# keyModule.net
KiCad netlist of a schematic drawn in Altium Designer
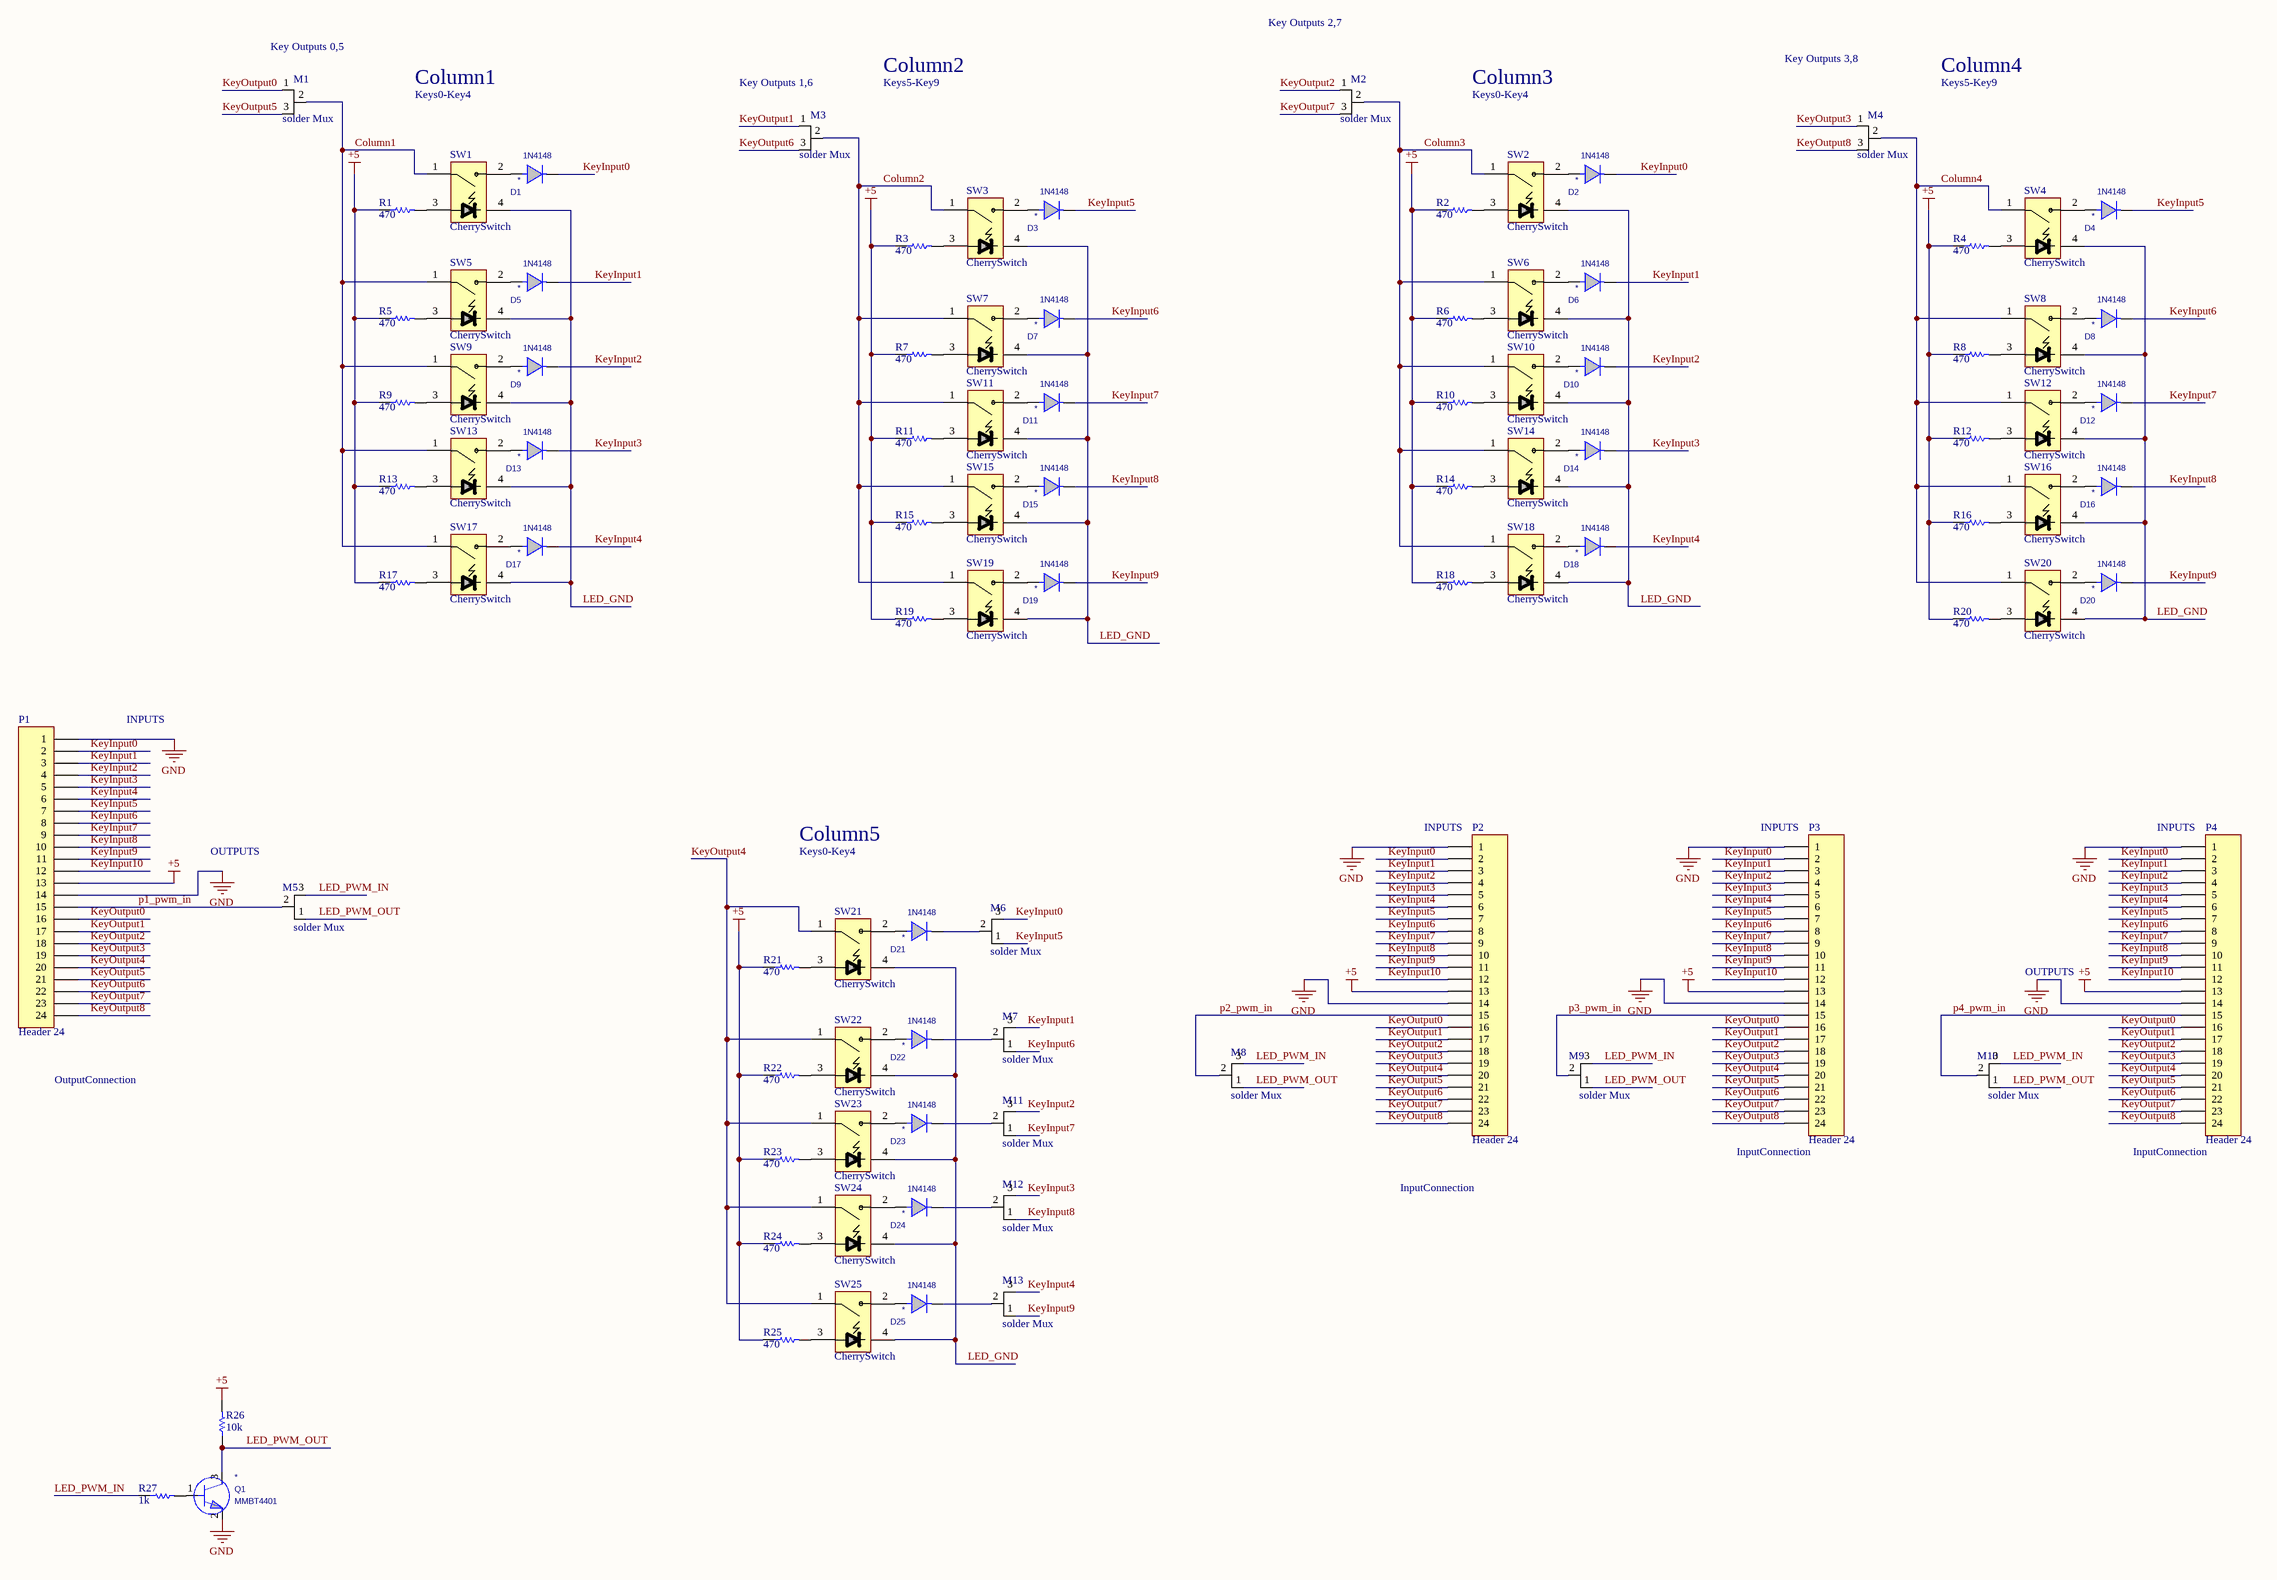
[diagram p0: keyModule.SchDoc]

(export (version "E")
  (design (tool "Eeschema 10.0.6"))
  (components
    (comp (ref "D1")
      (value "1N4148")
      (footprint "axial with SOD-323F")
      (description "Diode, 1N4148, 75V, 0.4 in., DO-35, 150mA, Switching, 500mW, Any")
      (fields (field (name "DNS") "*") (field (name "VOLTAGE") "75V") (field (name "CHECKEDBY") "B. Lyon"))
      (libsource (lib "bome") (part "1N4148"))
    )
    (comp (ref "D2")
      (value "1N4148")
      (footprint "axial with SOD-323F")
      (description "Diode, 1N4148, 75V, 0.4 in., DO-35, 150mA, Switching, 500mW, Any")
      (fields (field (name "DNS") "*") (field (name "VOLTAGE") "75V") (field (name "CHECKEDBY") "B. Lyon"))
      (libsource (lib "bome") (part "1N4148"))
    )
    (comp (ref "D3")
      (value "1N4148")
      (footprint "axial with SOD-323F")
      (description "Diode, 1N4148, 75V, 0.4 in., DO-35, 150mA, Switching, 500mW, Any")
      (fields (field (name "DNS") "*") (field (name "VOLTAGE") "75V") (field (name "CHECKEDBY") "B. Lyon"))
      (libsource (lib "bome") (part "1N4148"))
    )
    (comp (ref "D4")
      (value "1N4148")
      (footprint "axial with SOD-323F")
      (description "Diode, 1N4148, 75V, 0.4 in., DO-35, 150mA, Switching, 500mW, Any")
      (fields (field (name "DNS") "*") (field (name "VOLTAGE") "75V") (field (name "CHECKEDBY") "B. Lyon"))
      (libsource (lib "bome") (part "1N4148"))
    )
    (comp (ref "D5")
      (value "1N4148")
      (footprint "axial with SOD-323F")
      (description "Diode, 1N4148, 75V, 0.4 in., DO-35, 150mA, Switching, 500mW, Any")
      (fields (field (name "DNS") "*") (field (name "VOLTAGE") "75V") (field (name "CHECKEDBY") "B. Lyon"))
      (libsource (lib "bome") (part "1N4148"))
    )
    (comp (ref "D6")
      (value "1N4148")
      (footprint "axial with SOD-323F")
      (description "Diode, 1N4148, 75V, 0.4 in., DO-35, 150mA, Switching, 500mW, Any")
      (fields (field (name "DNS") "*") (field (name "VOLTAGE") "75V") (field (name "CHECKEDBY") "B. Lyon"))
      (libsource (lib "bome") (part "1N4148"))
    )
    (comp (ref "D7")
      (value "1N4148")
      (footprint "axial with SOD-323F")
      (description "Diode, 1N4148, 75V, 0.4 in., DO-35, 150mA, Switching, 500mW, Any")
      (fields (field (name "DNS") "*") (field (name "VOLTAGE") "75V") (field (name "CHECKEDBY") "B. Lyon"))
      (libsource (lib "bome") (part "1N4148"))
    )
    (comp (ref "D8")
      (value "1N4148")
      (footprint "axial with SOD-323F")
      (description "Diode, 1N4148, 75V, 0.4 in., DO-35, 150mA, Switching, 500mW, Any")
      (fields (field (name "DNS") "*") (field (name "VOLTAGE") "75V") (field (name "CHECKEDBY") "B. Lyon"))
      (libsource (lib "bome") (part "1N4148"))
    )
    (comp (ref "D9")
      (value "1N4148")
      (footprint "axial with SOD-323F")
      (description "Diode, 1N4148, 75V, 0.4 in., DO-35, 150mA, Switching, 500mW, Any")
      (fields (field (name "DNS") "*") (field (name "VOLTAGE") "75V") (field (name "CHECKEDBY") "B. Lyon"))
      (libsource (lib "bome") (part "1N4148"))
    )
    (comp (ref "D10")
      (value "1N4148")
      (footprint "axial with SOD-323F")
      (description "Diode, 1N4148, 75V, 0.4 in., DO-35, 150mA, Switching, 500mW, Any")
      (fields (field (name "DNS") "*") (field (name "VOLTAGE") "75V") (field (name "CHECKEDBY") "B. Lyon"))
      (libsource (lib "bome") (part "1N4148"))
    )
    (comp (ref "D11")
      (value "1N4148")
      (footprint "axial with SOD-323F")
      (description "Diode, 1N4148, 75V, 0.4 in., DO-35, 150mA, Switching, 500mW, Any")
      (fields (field (name "DNS") "*") (field (name "VOLTAGE") "75V") (field (name "CHECKEDBY") "B. Lyon"))
      (libsource (lib "bome") (part "1N4148"))
    )
    (comp (ref "D12")
      (value "1N4148")
      (footprint "axial with SOD-323F")
      (description "Diode, 1N4148, 75V, 0.4 in., DO-35, 150mA, Switching, 500mW, Any")
      (fields (field (name "DNS") "*") (field (name "VOLTAGE") "75V") (field (name "CHECKEDBY") "B. Lyon"))
      (libsource (lib "bome") (part "1N4148"))
    )
    (comp (ref "D13")
      (value "1N4148")
      (footprint "axial with SOD-323F")
      (description "Diode, 1N4148, 75V, 0.4 in., DO-35, 150mA, Switching, 500mW, Any")
      (fields (field (name "DNS") "*") (field (name "VOLTAGE") "75V") (field (name "CHECKEDBY") "B. Lyon"))
      (libsource (lib "bome") (part "1N4148"))
    )
    (comp (ref "D14")
      (value "1N4148")
      (footprint "axial with SOD-323F")
      (description "Diode, 1N4148, 75V, 0.4 in., DO-35, 150mA, Switching, 500mW, Any")
      (fields (field (name "DNS") "*") (field (name "VOLTAGE") "75V") (field (name "CHECKEDBY") "B. Lyon"))
      (libsource (lib "bome") (part "1N4148"))
    )
    (comp (ref "D15")
      (value "1N4148")
      (footprint "axial with SOD-323F")
      (description "Diode, 1N4148, 75V, 0.4 in., DO-35, 150mA, Switching, 500mW, Any")
      (fields (field (name "DNS") "*") (field (name "VOLTAGE") "75V") (field (name "CHECKEDBY") "B. Lyon"))
      (libsource (lib "bome") (part "1N4148"))
    )
    (comp (ref "D16")
      (value "1N4148")
      (footprint "axial with SOD-323F")
      (description "Diode, 1N4148, 75V, 0.4 in., DO-35, 150mA, Switching, 500mW, Any")
      (fields (field (name "DNS") "*") (field (name "VOLTAGE") "75V") (field (name "CHECKEDBY") "B. Lyon"))
      (libsource (lib "bome") (part "1N4148"))
    )
    (comp (ref "D17")
      (value "1N4148")
      (footprint "axial with SOD-323F")
      (description "Diode, 1N4148, 75V, 0.4 in., DO-35, 150mA, Switching, 500mW, Any")
      (fields (field (name "DNS") "*") (field (name "VOLTAGE") "75V") (field (name "CHECKEDBY") "B. Lyon"))
      (libsource (lib "bome") (part "1N4148"))
    )
    (comp (ref "D18")
      (value "1N4148")
      (footprint "axial with SOD-323F")
      (description "Diode, 1N4148, 75V, 0.4 in., DO-35, 150mA, Switching, 500mW, Any")
      (fields (field (name "DNS") "*") (field (name "VOLTAGE") "75V") (field (name "CHECKEDBY") "B. Lyon"))
      (libsource (lib "bome") (part "1N4148"))
    )
    (comp (ref "D19")
      (value "1N4148")
      (footprint "axial with SOD-323F")
      (description "Diode, 1N4148, 75V, 0.4 in., DO-35, 150mA, Switching, 500mW, Any")
      (fields (field (name "DNS") "*") (field (name "VOLTAGE") "75V") (field (name "CHECKEDBY") "B. Lyon"))
      (libsource (lib "bome") (part "1N4148"))
    )
    (comp (ref "D20")
      (value "1N4148")
      (footprint "axial with SOD-323F")
      (description "Diode, 1N4148, 75V, 0.4 in., DO-35, 150mA, Switching, 500mW, Any")
      (fields (field (name "DNS") "*") (field (name "VOLTAGE") "75V") (field (name "CHECKEDBY") "B. Lyon"))
      (libsource (lib "bome") (part "1N4148"))
    )
    (comp (ref "D21")
      (value "1N4148")
      (footprint "axial with SOD-323F")
      (description "Diode, 1N4148, 75V, 0.4 in., DO-35, 150mA, Switching, 500mW, Any")
      (fields (field (name "DNS") "*") (field (name "VOLTAGE") "75V") (field (name "CHECKEDBY") "B. Lyon"))
      (libsource (lib "bome") (part "1N4148"))
    )
    (comp (ref "D22")
      (value "1N4148")
      (footprint "axial with SOD-323F")
      (description "Diode, 1N4148, 75V, 0.4 in., DO-35, 150mA, Switching, 500mW, Any")
      (fields (field (name "DNS") "*") (field (name "VOLTAGE") "75V") (field (name "CHECKEDBY") "B. Lyon"))
      (libsource (lib "bome") (part "1N4148"))
    )
    (comp (ref "D23")
      (value "1N4148")
      (footprint "axial with SOD-323F")
      (description "Diode, 1N4148, 75V, 0.4 in., DO-35, 150mA, Switching, 500mW, Any")
      (fields (field (name "DNS") "*") (field (name "VOLTAGE") "75V") (field (name "CHECKEDBY") "B. Lyon"))
      (libsource (lib "bome") (part "1N4148"))
    )
    (comp (ref "D24")
      (value "1N4148")
      (footprint "axial with SOD-323F")
      (description "Diode, 1N4148, 75V, 0.4 in., DO-35, 150mA, Switching, 500mW, Any")
      (fields (field (name "DNS") "*") (field (name "VOLTAGE") "75V") (field (name "CHECKEDBY") "B. Lyon"))
      (libsource (lib "bome") (part "1N4148"))
    )
    (comp (ref "D25")
      (value "1N4148")
      (footprint "axial with SOD-323F")
      (description "Diode, 1N4148, 75V, 0.4 in., DO-35, 150mA, Switching, 500mW, Any")
      (fields (field (name "DNS") "*") (field (name "VOLTAGE") "75V") (field (name "CHECKEDBY") "B. Lyon"))
      (libsource (lib "bome") (part "1N4148"))
    )
    (comp (ref "M1")
      (value "solder Mux")
      (footprint "SolderSelect")
      (libsource (lib "mainBoardLib") (part "solder Mux"))
    )
    (comp (ref "M2")
      (value "solder Mux")
      (footprint "SolderSelect")
      (libsource (lib "mainBoardLib") (part "solder Mux"))
    )
    (comp (ref "M3")
      (value "solder Mux")
      (footprint "SolderSelect")
      (libsource (lib "mainBoardLib") (part "solder Mux"))
    )
    (comp (ref "M4")
      (value "solder Mux")
      (footprint "SolderSelect")
      (libsource (lib "mainBoardLib") (part "solder Mux"))
    )
    (comp (ref "M5")
      (value "solder Mux")
      (footprint "SolderSelect")
      (libsource (lib "mainBoardLib") (part "solder Mux"))
    )
    (comp (ref "M6")
      (value "solder Mux")
      (footprint "SolderSelect")
      (libsource (lib "mainBoardLib") (part "solder Mux"))
    )
    (comp (ref "M7")
      (value "solder Mux")
      (footprint "SolderSelect")
      (libsource (lib "mainBoardLib") (part "solder Mux"))
    )
    (comp (ref "M8")
      (value "solder Mux")
      (footprint "SolderSelect")
      (libsource (lib "mainBoardLib") (part "solder Mux"))
    )
    (comp (ref "M9")
      (value "solder Mux")
      (footprint "SolderSelect")
      (libsource (lib "mainBoardLib") (part "solder Mux"))
    )
    (comp (ref "M10")
      (value "solder Mux")
      (footprint "SolderSelect")
      (libsource (lib "mainBoardLib") (part "solder Mux"))
    )
    (comp (ref "M11")
      (value "solder Mux")
      (footprint "SolderSelect")
      (libsource (lib "mainBoardLib") (part "solder Mux"))
    )
    (comp (ref "M12")
      (value "solder Mux")
      (footprint "SolderSelect")
      (libsource (lib "mainBoardLib") (part "solder Mux"))
    )
    (comp (ref "M13")
      (value "solder Mux")
      (footprint "SolderSelect")
      (libsource (lib "mainBoardLib") (part "solder Mux"))
    )
    (comp (ref "P1")
      (value "Header 24")
      (footprint "HDR1X24")
      (description "Header, 24-Pin")
      (fields (field (name "PUBLISHER") "Altium Limited"))
      (libsource (lib "") (part "Header 24_1"))
    )
    (comp (ref "P2")
      (value "Header 24")
      (footprint "HDR1X24")
      (description "Header, 24-Pin")
      (fields (field (name "PUBLISHER") "Altium Limited"))
      (libsource (lib "Miscellaneous Connectors") (part "Header 24"))
    )
    (comp (ref "P3")
      (value "Header 24")
      (footprint "HDR1X24")
      (description "Header, 24-Pin")
      (fields (field (name "PUBLISHER") "Altium Limited"))
      (libsource (lib "Miscellaneous Connectors") (part "Header 24"))
    )
    (comp (ref "P4")
      (value "Header 24")
      (footprint "HDR1X24")
      (description "Header, 24-Pin")
      (fields (field (name "PUBLISHER") "Altium Limited"))
      (libsource (lib "Miscellaneous Connectors") (part "Header 24"))
    )
    (comp (ref "Q1")
      (value "MMBT4401")
      (footprint "SOT23-3")
      (description "Transistor, MMBT4401, 40V, SOT23-3, 500mA, NPN, Transistor, On Semi: MMBT4401LT1")
      (fields
        (field (name "DNS") "*")
        (field (name "VOLTAGE") "40V")
        (field (name "Comment") "NPN_TRANSISTOR")
        (field (name "CHECKEDBY") "gdeguzman")
        (field (name "CREATEDBY") "Mike Tyger")
        (field (name "LASTUPDATEDBY") "Mike Tyger")
      )
      (libsource (lib "bome") (part "NPN_TRANSISTOR"))
    )
    (comp (ref "R1")
      (value "470")
      (footprint "RESC2012L")
      (description "Semiconductor Resistor")
      (fields (field (name "Comment") "Res Semi") (field (name "PUBLISHER") "Altium Limited"))
      (libsource (lib "Miscellaneous Devices") (part "Res Semi"))
    )
    (comp (ref "R2")
      (value "470")
      (footprint "RESC2012L")
      (description "Semiconductor Resistor")
      (fields (field (name "Comment") "Res Semi") (field (name "PUBLISHER") "Altium Limited"))
      (libsource (lib "Miscellaneous Devices") (part "Res Semi"))
    )
    (comp (ref "R3")
      (value "470")
      (footprint "RESC2012L")
      (description "Semiconductor Resistor")
      (fields (field (name "Comment") "Res Semi") (field (name "PUBLISHER") "Altium Limited"))
      (libsource (lib "Miscellaneous Devices") (part "Res Semi"))
    )
    (comp (ref "R4")
      (value "470")
      (footprint "RESC2012L")
      (description "Semiconductor Resistor")
      (fields (field (name "Comment") "Res Semi") (field (name "PUBLISHER") "Altium Limited"))
      (libsource (lib "Miscellaneous Devices") (part "Res Semi"))
    )
    (comp (ref "R5")
      (value "470")
      (footprint "RESC2012L")
      (description "Semiconductor Resistor")
      (fields (field (name "Comment") "Res Semi") (field (name "PUBLISHER") "Altium Limited"))
      (libsource (lib "Miscellaneous Devices") (part "Res Semi"))
    )
    (comp (ref "R6")
      (value "470")
      (footprint "RESC2012L")
      (description "Semiconductor Resistor")
      (fields (field (name "Comment") "Res Semi") (field (name "PUBLISHER") "Altium Limited"))
      (libsource (lib "Miscellaneous Devices") (part "Res Semi"))
    )
    (comp (ref "R7")
      (value "470")
      (footprint "RESC2012L")
      (description "Semiconductor Resistor")
      (fields (field (name "Comment") "Res Semi") (field (name "PUBLISHER") "Altium Limited"))
      (libsource (lib "Miscellaneous Devices") (part "Res Semi"))
    )
    (comp (ref "R8")
      (value "470")
      (footprint "RESC2012L")
      (description "Semiconductor Resistor")
      (fields (field (name "Comment") "Res Semi") (field (name "PUBLISHER") "Altium Limited"))
      (libsource (lib "Miscellaneous Devices") (part "Res Semi"))
    )
    (comp (ref "R9")
      (value "470")
      (footprint "RESC2012L")
      (description "Semiconductor Resistor")
      (fields (field (name "Comment") "Res Semi") (field (name "PUBLISHER") "Altium Limited"))
      (libsource (lib "Miscellaneous Devices") (part "Res Semi"))
    )
    (comp (ref "R10")
      (value "470")
      (footprint "RESC2012L")
      (description "Semiconductor Resistor")
      (fields (field (name "Comment") "Res Semi") (field (name "PUBLISHER") "Altium Limited"))
      (libsource (lib "Miscellaneous Devices") (part "Res Semi"))
    )
    (comp (ref "R11")
      (value "470")
      (footprint "RESC2012L")
      (description "Semiconductor Resistor")
      (fields (field (name "Comment") "Res Semi") (field (name "PUBLISHER") "Altium Limited"))
      (libsource (lib "Miscellaneous Devices") (part "Res Semi"))
    )
    (comp (ref "R12")
      (value "470")
      (footprint "RESC2012L")
      (description "Semiconductor Resistor")
      (fields (field (name "Comment") "Res Semi") (field (name "PUBLISHER") "Altium Limited"))
      (libsource (lib "Miscellaneous Devices") (part "Res Semi"))
    )
    (comp (ref "R13")
      (value "470")
      (footprint "RESC2012L")
      (description "Semiconductor Resistor")
      (fields (field (name "Comment") "Res Semi") (field (name "PUBLISHER") "Altium Limited"))
      (libsource (lib "Miscellaneous Devices") (part "Res Semi"))
    )
    (comp (ref "R14")
      (value "470")
      (footprint "RESC2012L")
      (description "Semiconductor Resistor")
      (fields (field (name "Comment") "Res Semi") (field (name "PUBLISHER") "Altium Limited"))
      (libsource (lib "Miscellaneous Devices") (part "Res Semi"))
    )
    (comp (ref "R15")
      (value "470")
      (footprint "RESC2012L")
      (description "Semiconductor Resistor")
      (fields (field (name "Comment") "Res Semi") (field (name "PUBLISHER") "Altium Limited"))
      (libsource (lib "Miscellaneous Devices") (part "Res Semi"))
    )
    (comp (ref "R16")
      (value "470")
      (footprint "RESC2012L")
      (description "Semiconductor Resistor")
      (fields (field (name "Comment") "Res Semi") (field (name "PUBLISHER") "Altium Limited"))
      (libsource (lib "Miscellaneous Devices") (part "Res Semi"))
    )
    (comp (ref "R17")
      (value "470")
      (footprint "RESC2012L")
      (description "Semiconductor Resistor")
      (fields (field (name "Comment") "Res Semi") (field (name "PUBLISHER") "Altium Limited"))
      (libsource (lib "Miscellaneous Devices") (part "Res Semi"))
    )
    (comp (ref "R18")
      (value "470")
      (footprint "RESC2012L")
      (description "Semiconductor Resistor")
      (fields (field (name "Comment") "Res Semi") (field (name "PUBLISHER") "Altium Limited"))
      (libsource (lib "Miscellaneous Devices") (part "Res Semi"))
    )
    (comp (ref "R19")
      (value "470")
      (footprint "RESC2012L")
      (description "Semiconductor Resistor")
      (fields (field (name "Comment") "Res Semi") (field (name "PUBLISHER") "Altium Limited"))
      (libsource (lib "Miscellaneous Devices") (part "Res Semi"))
    )
    (comp (ref "R20")
      (value "470")
      (footprint "RESC2012L")
      (description "Semiconductor Resistor")
      (fields (field (name "Comment") "Res Semi") (field (name "PUBLISHER") "Altium Limited"))
      (libsource (lib "Miscellaneous Devices") (part "Res Semi"))
    )
    (comp (ref "R21")
      (value "470")
      (footprint "RESC2012L")
      (description "Semiconductor Resistor")
      (fields (field (name "Comment") "Res Semi") (field (name "PUBLISHER") "Altium Limited"))
      (libsource (lib "Miscellaneous Devices") (part "Res Semi"))
    )
    (comp (ref "R22")
      (value "470")
      (footprint "RESC2012L")
      (description "Semiconductor Resistor")
      (fields (field (name "Comment") "Res Semi") (field (name "PUBLISHER") "Altium Limited"))
      (libsource (lib "Miscellaneous Devices") (part "Res Semi"))
    )
    (comp (ref "R23")
      (value "470")
      (footprint "RESC2012L")
      (description "Semiconductor Resistor")
      (fields (field (name "Comment") "Res Semi") (field (name "PUBLISHER") "Altium Limited"))
      (libsource (lib "Miscellaneous Devices") (part "Res Semi"))
    )
    (comp (ref "R24")
      (value "470")
      (footprint "RESC2012L")
      (description "Semiconductor Resistor")
      (fields (field (name "Comment") "Res Semi") (field (name "PUBLISHER") "Altium Limited"))
      (libsource (lib "Miscellaneous Devices") (part "Res Semi"))
    )
    (comp (ref "R25")
      (value "470")
      (footprint "RESC2012L")
      (description "Semiconductor Resistor")
      (fields (field (name "Comment") "Res Semi") (field (name "PUBLISHER") "Altium Limited"))
      (libsource (lib "Miscellaneous Devices") (part "Res Semi"))
    )
    (comp (ref "R26")
      (value "10k")
      (footprint "RESC2012L")
      (description "Semiconductor Resistor")
      (fields (field (name "Comment") "Res Semi") (field (name "PUBLISHER") "Altium Limited"))
      (libsource (lib "Miscellaneous Devices") (part "Res Semi"))
    )
    (comp (ref "R27")
      (value "1k")
      (footprint "RESC2012L")
      (description "Semiconductor Resistor")
      (fields (field (name "Comment") "Res Semi") (field (name "PUBLISHER") "Altium Limited"))
      (libsource (lib "Miscellaneous Devices") (part "Res Semi"))
    )
    (comp (ref "SW1")
      (value "CherrySwitch")
      (footprint "CherryMxSwitch")
      (description "Cherry MX Switch layout")
      (libsource (lib "mainBoardLib") (part "CherrySwitch"))
    )
    (comp (ref "SW2")
      (value "CherrySwitch")
      (footprint "CherryMxSwitch")
      (description "Cherry MX Switch layout")
      (libsource (lib "mainBoardLib") (part "CherrySwitch"))
    )
    (comp (ref "SW3")
      (value "CherrySwitch")
      (footprint "CherryMxSwitch")
      (description "Cherry MX Switch layout")
      (libsource (lib "mainBoardLib") (part "CherrySwitch"))
    )
    (comp (ref "SW4")
      (value "CherrySwitch")
      (footprint "CherryMxSwitch")
      (description "Cherry MX Switch layout")
      (libsource (lib "mainBoardLib") (part "CherrySwitch"))
    )
    (comp (ref "SW5")
      (value "CherrySwitch")
      (footprint "CherryMxSwitch")
      (description "Cherry MX Switch layout")
      (libsource (lib "mainBoardLib") (part "CherrySwitch"))
    )
    (comp (ref "SW6")
      (value "CherrySwitch")
      (footprint "CherryMxSwitch")
      (description "Cherry MX Switch layout")
      (libsource (lib "mainBoardLib") (part "CherrySwitch"))
    )
    (comp (ref "SW7")
      (value "CherrySwitch")
      (footprint "CherryMxSwitch")
      (description "Cherry MX Switch layout")
      (libsource (lib "mainBoardLib") (part "CherrySwitch"))
    )
    (comp (ref "SW8")
      (value "CherrySwitch")
      (footprint "CherryMxSwitch")
      (description "Cherry MX Switch layout")
      (libsource (lib "mainBoardLib") (part "CherrySwitch"))
    )
    (comp (ref "SW9")
      (value "CherrySwitch")
      (footprint "CherryMxSwitch")
      (description "Cherry MX Switch layout")
      (libsource (lib "mainBoardLib") (part "CherrySwitch"))
    )
    (comp (ref "SW10")
      (value "CherrySwitch")
      (footprint "CherryMxSwitch")
      (description "Cherry MX Switch layout")
      (libsource (lib "mainBoardLib") (part "CherrySwitch"))
    )
    (comp (ref "SW11")
      (value "CherrySwitch")
      (footprint "CherryMxSwitch")
      (description "Cherry MX Switch layout")
      (libsource (lib "mainBoardLib") (part "CherrySwitch"))
    )
    (comp (ref "SW12")
      (value "CherrySwitch")
      (footprint "CherryMxSwitch")
      (description "Cherry MX Switch layout")
      (libsource (lib "mainBoardLib") (part "CherrySwitch"))
    )
    (comp (ref "SW13")
      (value "CherrySwitch")
      (footprint "CherryMxSwitch")
      (description "Cherry MX Switch layout")
      (libsource (lib "mainBoardLib") (part "CherrySwitch"))
    )
    (comp (ref "SW14")
      (value "CherrySwitch")
      (footprint "CherryMxSwitch")
      (description "Cherry MX Switch layout")
      (libsource (lib "mainBoardLib") (part "CherrySwitch"))
    )
    (comp (ref "SW15")
      (value "CherrySwitch")
      (footprint "CherryMxSwitch")
      (description "Cherry MX Switch layout")
      (libsource (lib "mainBoardLib") (part "CherrySwitch"))
    )
    (comp (ref "SW16")
      (value "CherrySwitch")
      (footprint "CherryMxSwitch")
      (description "Cherry MX Switch layout")
      (libsource (lib "mainBoardLib") (part "CherrySwitch"))
    )
    (comp (ref "SW17")
      (value "CherrySwitch")
      (footprint "CherryMxSwitch")
      (description "Cherry MX Switch layout")
      (libsource (lib "mainBoardLib") (part "CherrySwitch"))
    )
    (comp (ref "SW18")
      (value "CherrySwitch")
      (footprint "CherryMxSwitch")
      (description "Cherry MX Switch layout")
      (libsource (lib "mainBoardLib") (part "CherrySwitch"))
    )
    (comp (ref "SW19")
      (value "CherrySwitch")
      (footprint "CherryMxSwitch")
      (description "Cherry MX Switch layout")
      (libsource (lib "mainBoardLib") (part "CherrySwitch"))
    )
    (comp (ref "SW20")
      (value "CherrySwitch")
      (footprint "CherryMxSwitch")
      (description "Cherry MX Switch layout")
      (libsource (lib "mainBoardLib") (part "CherrySwitch"))
    )
    (comp (ref "SW21")
      (value "CherrySwitch")
      (footprint "CherryMxSwitch")
      (description "Cherry MX Switch layout")
      (libsource (lib "mainBoardLib") (part "CherrySwitch"))
    )
    (comp (ref "SW22")
      (value "CherrySwitch")
      (footprint "CherryMxSwitch")
      (description "Cherry MX Switch layout")
      (libsource (lib "mainBoardLib") (part "CherrySwitch"))
    )
    (comp (ref "SW23")
      (value "CherrySwitch")
      (footprint "CherryMxSwitch")
      (description "Cherry MX Switch layout")
      (libsource (lib "mainBoardLib") (part "CherrySwitch"))
    )
    (comp (ref "SW24")
      (value "CherrySwitch")
      (footprint "CherryMxSwitch")
      (description "Cherry MX Switch layout")
      (libsource (lib "mainBoardLib") (part "CherrySwitch"))
    )
    (comp (ref "SW25")
      (value "CherrySwitch")
      (footprint "CherryMxSwitch")
      (description "Cherry MX Switch layout")
      (libsource (lib "mainBoardLib") (part "CherrySwitch"))
    )
  )
  (nets
    (net (code "1") (name "+5") (class "Default")
      (node (ref "P1") (pin "13") (pinfunction "13_13") (pintype "passive"))
      (node (ref "P2") (pin "13") (pinfunction "13_13") (pintype "passive"))
      (node (ref "P3") (pin "13") (pinfunction "13_13") (pintype "passive"))
      (node (ref "P4") (pin "13") (pinfunction "13_13") (pintype "passive"))
      (node (ref "R1") (pin "1") (pinfunction "1_1") (pintype "passive"))
      (node (ref "R10") (pin "1") (pinfunction "1_1") (pintype "passive"))
      (node (ref "R11") (pin "1") (pinfunction "1_1") (pintype "passive"))
      (node (ref "R12") (pin "1") (pinfunction "1_1") (pintype "passive"))
      (node (ref "R13") (pin "1") (pinfunction "1_1") (pintype "passive"))
      (node (ref "R14") (pin "1") (pinfunction "1_1") (pintype "passive"))
      (node (ref "R15") (pin "1") (pinfunction "1_1") (pintype "passive"))
      (node (ref "R16") (pin "1") (pinfunction "1_1") (pintype "passive"))
      (node (ref "R17") (pin "1") (pinfunction "1_1") (pintype "passive"))
      (node (ref "R18") (pin "1") (pinfunction "1_1") (pintype "passive"))
      (node (ref "R19") (pin "1") (pinfunction "1_1") (pintype "passive"))
      (node (ref "R2") (pin "1") (pinfunction "1_1") (pintype "passive"))
      (node (ref "R20") (pin "1") (pinfunction "1_1") (pintype "passive"))
      (node (ref "R21") (pin "1") (pinfunction "1_1") (pintype "passive"))
      (node (ref "R22") (pin "1") (pinfunction "1_1") (pintype "passive"))
      (node (ref "R23") (pin "1") (pinfunction "1_1") (pintype "passive"))
      (node (ref "R24") (pin "1") (pinfunction "1_1") (pintype "passive"))
      (node (ref "R25") (pin "1") (pinfunction "1_1") (pintype "passive"))
      (node (ref "R26") (pin "2") (pinfunction "2_2") (pintype "passive"))
      (node (ref "R3") (pin "1") (pinfunction "1_1") (pintype "passive"))
      (node (ref "R4") (pin "1") (pinfunction "1_1") (pintype "passive"))
      (node (ref "R5") (pin "1") (pinfunction "1_1") (pintype "passive"))
      (node (ref "R6") (pin "1") (pinfunction "1_1") (pintype "passive"))
      (node (ref "R7") (pin "1") (pinfunction "1_1") (pintype "passive"))
      (node (ref "R8") (pin "1") (pinfunction "1_1") (pintype "passive"))
      (node (ref "R9") (pin "1") (pinfunction "1_1") (pintype "passive"))
    )
    (net (code "2") (name "/Column1") (class "Default")
      (node (ref "M1") (pin "2") (pinfunction "2_2") (pintype "passive"))
      (node (ref "SW1") (pin "1") (pinfunction "1_1") (pintype "passive"))
      (node (ref "SW13") (pin "1") (pinfunction "1_1") (pintype "passive"))
      (node (ref "SW17") (pin "1") (pinfunction "1_1") (pintype "passive"))
      (node (ref "SW5") (pin "1") (pinfunction "1_1") (pintype "passive"))
      (node (ref "SW9") (pin "1") (pinfunction "1_1") (pintype "passive"))
    )
    (net (code "3") (name "/Column2") (class "Default")
      (node (ref "M3") (pin "2") (pinfunction "2_2") (pintype "passive"))
      (node (ref "SW11") (pin "1") (pinfunction "1_1") (pintype "passive"))
      (node (ref "SW15") (pin "1") (pinfunction "1_1") (pintype "passive"))
      (node (ref "SW19") (pin "1") (pinfunction "1_1") (pintype "passive"))
      (node (ref "SW3") (pin "1") (pinfunction "1_1") (pintype "passive"))
      (node (ref "SW7") (pin "1") (pinfunction "1_1") (pintype "passive"))
    )
    (net (code "4") (name "/Column3") (class "Default")
      (node (ref "M2") (pin "2") (pinfunction "2_2") (pintype "passive"))
      (node (ref "SW10") (pin "1") (pinfunction "1_1") (pintype "passive"))
      (node (ref "SW14") (pin "1") (pinfunction "1_1") (pintype "passive"))
      (node (ref "SW18") (pin "1") (pinfunction "1_1") (pintype "passive"))
      (node (ref "SW2") (pin "1") (pinfunction "1_1") (pintype "passive"))
      (node (ref "SW6") (pin "1") (pinfunction "1_1") (pintype "passive"))
    )
    (net (code "5") (name "/Column4") (class "Default")
      (node (ref "M4") (pin "2") (pinfunction "2_2") (pintype "passive"))
      (node (ref "SW12") (pin "1") (pinfunction "1_1") (pintype "passive"))
      (node (ref "SW16") (pin "1") (pinfunction "1_1") (pintype "passive"))
      (node (ref "SW20") (pin "1") (pinfunction "1_1") (pintype "passive"))
      (node (ref "SW4") (pin "1") (pinfunction "1_1") (pintype "passive"))
      (node (ref "SW8") (pin "1") (pinfunction "1_1") (pintype "passive"))
    )
    (net (code "6") (name "/KeyInput0") (class "Default")
      (node (ref "D1") (pin "1") (pinfunction "CATHODE_1") (pintype "passive"))
      (node (ref "D2") (pin "1") (pinfunction "CATHODE_1") (pintype "passive"))
      (node (ref "M6") (pin "3") (pinfunction "3_3") (pintype "passive"))
      (node (ref "P1") (pin "2") (pinfunction "2_2") (pintype "passive"))
      (node (ref "P2") (pin "2") (pinfunction "2_2") (pintype "passive"))
      (node (ref "P3") (pin "2") (pinfunction "2_2") (pintype "passive"))
      (node (ref "P4") (pin "2") (pinfunction "2_2") (pintype "passive"))
    )
    (net (code "7") (name "/KeyInput1") (class "Default")
      (node (ref "D5") (pin "1") (pinfunction "CATHODE_1") (pintype "passive"))
      (node (ref "D6") (pin "1") (pinfunction "CATHODE_1") (pintype "passive"))
      (node (ref "M7") (pin "3") (pinfunction "3_3") (pintype "passive"))
      (node (ref "P1") (pin "3") (pinfunction "3_3") (pintype "passive"))
      (node (ref "P2") (pin "3") (pinfunction "3_3") (pintype "passive"))
      (node (ref "P3") (pin "3") (pinfunction "3_3") (pintype "passive"))
      (node (ref "P4") (pin "3") (pinfunction "3_3") (pintype "passive"))
    )
    (net (code "8") (name "/KeyInput2") (class "Default")
      (node (ref "D10") (pin "1") (pinfunction "CATHODE_1") (pintype "passive"))
      (node (ref "D9") (pin "1") (pinfunction "CATHODE_1") (pintype "passive"))
      (node (ref "M11") (pin "3") (pinfunction "3_3") (pintype "passive"))
      (node (ref "P1") (pin "4") (pinfunction "4_4") (pintype "passive"))
      (node (ref "P2") (pin "4") (pinfunction "4_4") (pintype "passive"))
      (node (ref "P3") (pin "4") (pinfunction "4_4") (pintype "passive"))
      (node (ref "P4") (pin "4") (pinfunction "4_4") (pintype "passive"))
    )
    (net (code "9") (name "/KeyInput3") (class "Default")
      (node (ref "D13") (pin "1") (pinfunction "CATHODE_1") (pintype "passive"))
      (node (ref "D14") (pin "1") (pinfunction "CATHODE_1") (pintype "passive"))
      (node (ref "M12") (pin "3") (pinfunction "3_3") (pintype "passive"))
      (node (ref "P1") (pin "5") (pinfunction "5_5") (pintype "passive"))
      (node (ref "P2") (pin "5") (pinfunction "5_5") (pintype "passive"))
      (node (ref "P3") (pin "5") (pinfunction "5_5") (pintype "passive"))
      (node (ref "P4") (pin "5") (pinfunction "5_5") (pintype "passive"))
    )
    (net (code "10") (name "/KeyInput4") (class "Default")
      (node (ref "D17") (pin "1") (pinfunction "CATHODE_1") (pintype "passive"))
      (node (ref "D18") (pin "1") (pinfunction "CATHODE_1") (pintype "passive"))
      (node (ref "M13") (pin "3") (pinfunction "3_3") (pintype "passive"))
      (node (ref "P1") (pin "6") (pinfunction "6_6") (pintype "passive"))
      (node (ref "P2") (pin "6") (pinfunction "6_6") (pintype "passive"))
      (node (ref "P3") (pin "6") (pinfunction "6_6") (pintype "passive"))
      (node (ref "P4") (pin "6") (pinfunction "6_6") (pintype "passive"))
    )
    (net (code "11") (name "/KeyInput5") (class "Default")
      (node (ref "D3") (pin "1") (pinfunction "CATHODE_1") (pintype "passive"))
      (node (ref "D4") (pin "1") (pinfunction "CATHODE_1") (pintype "passive"))
      (node (ref "M6") (pin "1") (pinfunction "1_1") (pintype "passive"))
      (node (ref "P1") (pin "7") (pinfunction "7_7") (pintype "passive"))
      (node (ref "P2") (pin "7") (pinfunction "7_7") (pintype "passive"))
      (node (ref "P3") (pin "7") (pinfunction "7_7") (pintype "passive"))
      (node (ref "P4") (pin "7") (pinfunction "7_7") (pintype "passive"))
    )
    (net (code "12") (name "/KeyInput6") (class "Default")
      (node (ref "D7") (pin "1") (pinfunction "CATHODE_1") (pintype "passive"))
      (node (ref "D8") (pin "1") (pinfunction "CATHODE_1") (pintype "passive"))
      (node (ref "M7") (pin "1") (pinfunction "1_1") (pintype "passive"))
      (node (ref "P1") (pin "8") (pinfunction "8_8") (pintype "passive"))
      (node (ref "P2") (pin "8") (pinfunction "8_8") (pintype "passive"))
      (node (ref "P3") (pin "8") (pinfunction "8_8") (pintype "passive"))
      (node (ref "P4") (pin "8") (pinfunction "8_8") (pintype "passive"))
    )
    (net (code "13") (name "/KeyInput7") (class "Default")
      (node (ref "D11") (pin "1") (pinfunction "CATHODE_1") (pintype "passive"))
      (node (ref "D12") (pin "1") (pinfunction "CATHODE_1") (pintype "passive"))
      (node (ref "M11") (pin "1") (pinfunction "1_1") (pintype "passive"))
      (node (ref "P1") (pin "9") (pinfunction "9_9") (pintype "passive"))
      (node (ref "P2") (pin "9") (pinfunction "9_9") (pintype "passive"))
      (node (ref "P3") (pin "9") (pinfunction "9_9") (pintype "passive"))
      (node (ref "P4") (pin "9") (pinfunction "9_9") (pintype "passive"))
    )
    (net (code "14") (name "/KeyInput8") (class "Default")
      (node (ref "D15") (pin "1") (pinfunction "CATHODE_1") (pintype "passive"))
      (node (ref "D16") (pin "1") (pinfunction "CATHODE_1") (pintype "passive"))
      (node (ref "M12") (pin "1") (pinfunction "1_1") (pintype "passive"))
      (node (ref "P1") (pin "10") (pinfunction "10_10") (pintype "passive"))
      (node (ref "P2") (pin "10") (pinfunction "10_10") (pintype "passive"))
      (node (ref "P3") (pin "10") (pinfunction "10_10") (pintype "passive"))
      (node (ref "P4") (pin "10") (pinfunction "10_10") (pintype "passive"))
    )
    (net (code "15") (name "/KeyInput9") (class "Default")
      (node (ref "D19") (pin "1") (pinfunction "CATHODE_1") (pintype "passive"))
      (node (ref "D20") (pin "1") (pinfunction "CATHODE_1") (pintype "passive"))
      (node (ref "M13") (pin "1") (pinfunction "1_1") (pintype "passive"))
      (node (ref "P1") (pin "11") (pinfunction "11_11") (pintype "passive"))
      (node (ref "P2") (pin "11") (pinfunction "11_11") (pintype "passive"))
      (node (ref "P3") (pin "11") (pinfunction "11_11") (pintype "passive"))
      (node (ref "P4") (pin "11") (pinfunction "11_11") (pintype "passive"))
    )
    (net (code "16") (name "/KeyInput10") (class "Default")
      (node (ref "P1") (pin "12") (pinfunction "12_12") (pintype "passive"))
      (node (ref "P2") (pin "12") (pinfunction "12_12") (pintype "passive"))
      (node (ref "P3") (pin "12") (pinfunction "12_12") (pintype "passive"))
      (node (ref "P4") (pin "12") (pinfunction "12_12") (pintype "passive"))
    )
    (net (code "17") (name "/KeyOutput0") (class "Default")
      (node (ref "M1") (pin "1") (pinfunction "1_1") (pintype "passive"))
      (node (ref "P1") (pin "16") (pinfunction "16_16") (pintype "passive"))
      (node (ref "P2") (pin "16") (pinfunction "16_16") (pintype "passive"))
      (node (ref "P3") (pin "16") (pinfunction "16_16") (pintype "passive"))
      (node (ref "P4") (pin "16") (pinfunction "16_16") (pintype "passive"))
    )
    (net (code "18") (name "/KeyOutput1") (class "Default")
      (node (ref "M3") (pin "1") (pinfunction "1_1") (pintype "passive"))
      (node (ref "P1") (pin "17") (pinfunction "17_17") (pintype "passive"))
      (node (ref "P2") (pin "17") (pinfunction "17_17") (pintype "passive"))
      (node (ref "P3") (pin "17") (pinfunction "17_17") (pintype "passive"))
      (node (ref "P4") (pin "17") (pinfunction "17_17") (pintype "passive"))
    )
    (net (code "19") (name "/KeyOutput2") (class "Default")
      (node (ref "M2") (pin "1") (pinfunction "1_1") (pintype "passive"))
      (node (ref "P1") (pin "18") (pinfunction "18_18") (pintype "passive"))
      (node (ref "P2") (pin "18") (pinfunction "18_18") (pintype "passive"))
      (node (ref "P3") (pin "18") (pinfunction "18_18") (pintype "passive"))
      (node (ref "P4") (pin "18") (pinfunction "18_18") (pintype "passive"))
    )
    (net (code "20") (name "/KeyOutput3") (class "Default")
      (node (ref "M4") (pin "1") (pinfunction "1_1") (pintype "passive"))
      (node (ref "P1") (pin "19") (pinfunction "19_19") (pintype "passive"))
      (node (ref "P2") (pin "19") (pinfunction "19_19") (pintype "passive"))
      (node (ref "P3") (pin "19") (pinfunction "19_19") (pintype "passive"))
      (node (ref "P4") (pin "19") (pinfunction "19_19") (pintype "passive"))
    )
    (net (code "21") (name "/KeyOutput4") (class "Default")
      (node (ref "P1") (pin "20") (pinfunction "20_20") (pintype "passive"))
      (node (ref "P2") (pin "20") (pinfunction "20_20") (pintype "passive"))
      (node (ref "P3") (pin "20") (pinfunction "20_20") (pintype "passive"))
      (node (ref "P4") (pin "20") (pinfunction "20_20") (pintype "passive"))
      (node (ref "SW21") (pin "1") (pinfunction "1_1") (pintype "passive"))
      (node (ref "SW22") (pin "1") (pinfunction "1_1") (pintype "passive"))
      (node (ref "SW23") (pin "1") (pinfunction "1_1") (pintype "passive"))
      (node (ref "SW24") (pin "1") (pinfunction "1_1") (pintype "passive"))
      (node (ref "SW25") (pin "1") (pinfunction "1_1") (pintype "passive"))
    )
    (net (code "22") (name "/KeyOutput5") (class "Default")
      (node (ref "M1") (pin "3") (pinfunction "3_3") (pintype "passive"))
      (node (ref "P1") (pin "21") (pinfunction "21_21") (pintype "passive"))
      (node (ref "P2") (pin "21") (pinfunction "21_21") (pintype "passive"))
      (node (ref "P3") (pin "21") (pinfunction "21_21") (pintype "passive"))
      (node (ref "P4") (pin "21") (pinfunction "21_21") (pintype "passive"))
    )
    (net (code "23") (name "/KeyOutput6") (class "Default")
      (node (ref "M3") (pin "3") (pinfunction "3_3") (pintype "passive"))
      (node (ref "P1") (pin "22") (pinfunction "22_22") (pintype "passive"))
      (node (ref "P2") (pin "22") (pinfunction "22_22") (pintype "passive"))
      (node (ref "P3") (pin "22") (pinfunction "22_22") (pintype "passive"))
      (node (ref "P4") (pin "22") (pinfunction "22_22") (pintype "passive"))
    )
    (net (code "24") (name "/KeyOutput7") (class "Default")
      (node (ref "M2") (pin "3") (pinfunction "3_3") (pintype "passive"))
      (node (ref "P1") (pin "23") (pinfunction "23_23") (pintype "passive"))
      (node (ref "P2") (pin "23") (pinfunction "23_23") (pintype "passive"))
      (node (ref "P3") (pin "23") (pinfunction "23_23") (pintype "passive"))
      (node (ref "P4") (pin "23") (pinfunction "23_23") (pintype "passive"))
    )
    (net (code "25") (name "/KeyOutput8") (class "Default")
      (node (ref "M4") (pin "3") (pinfunction "3_3") (pintype "passive"))
      (node (ref "P1") (pin "24") (pinfunction "24_24") (pintype "passive"))
      (node (ref "P2") (pin "24") (pinfunction "24_24") (pintype "passive"))
      (node (ref "P3") (pin "24") (pinfunction "24_24") (pintype "passive"))
      (node (ref "P4") (pin "24") (pinfunction "24_24") (pintype "passive"))
    )
    (net (code "26") (name "/LED_GND") (class "Default")
      (node (ref "SW1") (pin "4") (pinfunction "4_4") (pintype "passive"))
      (node (ref "SW10") (pin "4") (pinfunction "4_4") (pintype "passive"))
      (node (ref "SW11") (pin "4") (pinfunction "4_4") (pintype "passive"))
      (node (ref "SW12") (pin "4") (pinfunction "4_4") (pintype "passive"))
      (node (ref "SW13") (pin "4") (pinfunction "4_4") (pintype "passive"))
      (node (ref "SW14") (pin "4") (pinfunction "4_4") (pintype "passive"))
      (node (ref "SW15") (pin "4") (pinfunction "4_4") (pintype "passive"))
      (node (ref "SW16") (pin "4") (pinfunction "4_4") (pintype "passive"))
      (node (ref "SW17") (pin "4") (pinfunction "4_4") (pintype "passive"))
      (node (ref "SW18") (pin "4") (pinfunction "4_4") (pintype "passive"))
      (node (ref "SW19") (pin "4") (pinfunction "4_4") (pintype "passive"))
      (node (ref "SW2") (pin "4") (pinfunction "4_4") (pintype "passive"))
      (node (ref "SW20") (pin "4") (pinfunction "4_4") (pintype "passive"))
      (node (ref "SW21") (pin "4") (pinfunction "4_4") (pintype "passive"))
      (node (ref "SW22") (pin "4") (pinfunction "4_4") (pintype "passive"))
      (node (ref "SW23") (pin "4") (pinfunction "4_4") (pintype "passive"))
      (node (ref "SW24") (pin "4") (pinfunction "4_4") (pintype "passive"))
      (node (ref "SW25") (pin "4") (pinfunction "4_4") (pintype "passive"))
      (node (ref "SW3") (pin "4") (pinfunction "4_4") (pintype "passive"))
      (node (ref "SW4") (pin "4") (pinfunction "4_4") (pintype "passive"))
      (node (ref "SW5") (pin "4") (pinfunction "4_4") (pintype "passive"))
      (node (ref "SW6") (pin "4") (pinfunction "4_4") (pintype "passive"))
      (node (ref "SW7") (pin "4") (pinfunction "4_4") (pintype "passive"))
      (node (ref "SW8") (pin "4") (pinfunction "4_4") (pintype "passive"))
      (node (ref "SW9") (pin "4") (pinfunction "4_4") (pintype "passive"))
    )
    (net (code "27") (name "/LED_PWM_IN") (class "Default")
      (node (ref "M10") (pin "3") (pinfunction "3_3") (pintype "passive"))
      (node (ref "M5") (pin "3") (pinfunction "3_3") (pintype "passive"))
      (node (ref "M8") (pin "3") (pinfunction "3_3") (pintype "passive"))
      (node (ref "M9") (pin "3") (pinfunction "3_3") (pintype "passive"))
      (node (ref "R27") (pin "1") (pinfunction "1_1") (pintype "passive"))
    )
    (net (code "28") (name "/LED_PWM_OUT") (class "Default")
      (node (ref "M10") (pin "1") (pinfunction "1_1") (pintype "passive"))
      (node (ref "M5") (pin "1") (pinfunction "1_1") (pintype "passive"))
      (node (ref "M8") (pin "1") (pinfunction "1_1") (pintype "passive"))
      (node (ref "M9") (pin "1") (pinfunction "1_1") (pintype "passive"))
      (node (ref "Q1") (pin "3") (pinfunction "collector_3") (pintype "passive"))
      (node (ref "R26") (pin "1") (pinfunction "1_1") (pintype "passive"))
    )
    (net (code "29") (name "/p1_pwm_in") (class "Default")
      (node (ref "M5") (pin "2") (pinfunction "2_2") (pintype "passive"))
      (node (ref "P1") (pin "15") (pinfunction "15_15") (pintype "passive"))
    )
    (net (code "30") (name "/p2_pwm_in") (class "Default")
      (node (ref "M8") (pin "2") (pinfunction "2_2") (pintype "passive"))
      (node (ref "P2") (pin "15") (pinfunction "15_15") (pintype "passive"))
    )
    (net (code "31") (name "/p3_pwm_in") (class "Default")
      (node (ref "M9") (pin "2") (pinfunction "2_2") (pintype "passive"))
      (node (ref "P3") (pin "15") (pinfunction "15_15") (pintype "passive"))
    )
    (net (code "32") (name "/p4_pwm_in") (class "Default")
      (node (ref "M10") (pin "2") (pinfunction "2_2") (pintype "passive"))
      (node (ref "P4") (pin "15") (pinfunction "15_15") (pintype "passive"))
    )
    (net (code "33") (name "GND") (class "Default")
      (node (ref "P1") (pin "1") (pinfunction "1_1") (pintype "passive"))
      (node (ref "P1") (pin "14") (pinfunction "14_14") (pintype "passive"))
      (node (ref "P2") (pin "1") (pinfunction "1_1") (pintype "passive"))
      (node (ref "P2") (pin "14") (pinfunction "14_14") (pintype "passive"))
      (node (ref "P3") (pin "1") (pinfunction "1_1") (pintype "passive"))
      (node (ref "P3") (pin "14") (pinfunction "14_14") (pintype "passive"))
      (node (ref "P4") (pin "1") (pinfunction "1_1") (pintype "passive"))
      (node (ref "P4") (pin "14") (pinfunction "14_14") (pintype "passive"))
      (node (ref "Q1") (pin "2") (pinfunction "emitter_2") (pintype "passive"))
    )
    (net (code "34") (name "Net-(D1-ANODE)") (class "Default")
      (node (ref "D1") (pin "2") (pinfunction "ANODE_2") (pintype "passive"))
      (node (ref "SW1") (pin "2") (pinfunction "2_2") (pintype "passive"))
    )
    (net (code "35") (name "Net-(D2-ANODE)") (class "Default")
      (node (ref "D2") (pin "2") (pinfunction "ANODE_2") (pintype "passive"))
      (node (ref "SW2") (pin "2") (pinfunction "2_2") (pintype "passive"))
    )
    (net (code "36") (name "Net-(D3-ANODE)") (class "Default")
      (node (ref "D3") (pin "2") (pinfunction "ANODE_2") (pintype "passive"))
      (node (ref "SW3") (pin "2") (pinfunction "2_2") (pintype "passive"))
    )
    (net (code "37") (name "Net-(D4-ANODE)") (class "Default")
      (node (ref "D4") (pin "2") (pinfunction "ANODE_2") (pintype "passive"))
      (node (ref "SW4") (pin "2") (pinfunction "2_2") (pintype "passive"))
    )
    (net (code "38") (name "Net-(D5-ANODE)") (class "Default")
      (node (ref "D5") (pin "2") (pinfunction "ANODE_2") (pintype "passive"))
      (node (ref "SW5") (pin "2") (pinfunction "2_2") (pintype "passive"))
    )
    (net (code "39") (name "Net-(D6-ANODE)") (class "Default")
      (node (ref "D6") (pin "2") (pinfunction "ANODE_2") (pintype "passive"))
      (node (ref "SW6") (pin "2") (pinfunction "2_2") (pintype "passive"))
    )
    (net (code "40") (name "Net-(D7-ANODE)") (class "Default")
      (node (ref "D7") (pin "2") (pinfunction "ANODE_2") (pintype "passive"))
      (node (ref "SW7") (pin "2") (pinfunction "2_2") (pintype "passive"))
    )
    (net (code "41") (name "Net-(D8-ANODE)") (class "Default")
      (node (ref "D8") (pin "2") (pinfunction "ANODE_2") (pintype "passive"))
      (node (ref "SW8") (pin "2") (pinfunction "2_2") (pintype "passive"))
    )
    (net (code "42") (name "Net-(D9-ANODE)") (class "Default")
      (node (ref "D9") (pin "2") (pinfunction "ANODE_2") (pintype "passive"))
      (node (ref "SW9") (pin "2") (pinfunction "2_2") (pintype "passive"))
    )
    (net (code "43") (name "Net-(D10-ANODE)") (class "Default")
      (node (ref "D10") (pin "2") (pinfunction "ANODE_2") (pintype "passive"))
      (node (ref "SW10") (pin "2") (pinfunction "2_2") (pintype "passive"))
    )
    (net (code "44") (name "Net-(D11-ANODE)") (class "Default")
      (node (ref "D11") (pin "2") (pinfunction "ANODE_2") (pintype "passive"))
      (node (ref "SW11") (pin "2") (pinfunction "2_2") (pintype "passive"))
    )
    (net (code "45") (name "Net-(D12-ANODE)") (class "Default")
      (node (ref "D12") (pin "2") (pinfunction "ANODE_2") (pintype "passive"))
      (node (ref "SW12") (pin "2") (pinfunction "2_2") (pintype "passive"))
    )
    (net (code "46") (name "Net-(D13-ANODE)") (class "Default")
      (node (ref "D13") (pin "2") (pinfunction "ANODE_2") (pintype "passive"))
      (node (ref "SW13") (pin "2") (pinfunction "2_2") (pintype "passive"))
    )
    (net (code "47") (name "Net-(D14-ANODE)") (class "Default")
      (node (ref "D14") (pin "2") (pinfunction "ANODE_2") (pintype "passive"))
      (node (ref "SW14") (pin "2") (pinfunction "2_2") (pintype "passive"))
    )
    (net (code "48") (name "Net-(D15-ANODE)") (class "Default")
      (node (ref "D15") (pin "2") (pinfunction "ANODE_2") (pintype "passive"))
      (node (ref "SW15") (pin "2") (pinfunction "2_2") (pintype "passive"))
    )
    (net (code "49") (name "Net-(D16-ANODE)") (class "Default")
      (node (ref "D16") (pin "2") (pinfunction "ANODE_2") (pintype "passive"))
      (node (ref "SW16") (pin "2") (pinfunction "2_2") (pintype "passive"))
    )
    (net (code "50") (name "Net-(D17-ANODE)") (class "Default")
      (node (ref "D17") (pin "2") (pinfunction "ANODE_2") (pintype "passive"))
      (node (ref "SW17") (pin "2") (pinfunction "2_2") (pintype "passive"))
    )
    (net (code "51") (name "Net-(D18-ANODE)") (class "Default")
      (node (ref "D18") (pin "2") (pinfunction "ANODE_2") (pintype "passive"))
      (node (ref "SW18") (pin "2") (pinfunction "2_2") (pintype "passive"))
    )
    (net (code "52") (name "Net-(D19-ANODE)") (class "Default")
      (node (ref "D19") (pin "2") (pinfunction "ANODE_2") (pintype "passive"))
      (node (ref "SW19") (pin "2") (pinfunction "2_2") (pintype "passive"))
    )
    (net (code "53") (name "Net-(D20-ANODE)") (class "Default")
      (node (ref "D20") (pin "2") (pinfunction "ANODE_2") (pintype "passive"))
      (node (ref "SW20") (pin "2") (pinfunction "2_2") (pintype "passive"))
    )
    (net (code "54") (name "Net-(D21-ANODE)") (class "Default")
      (node (ref "D21") (pin "2") (pinfunction "ANODE_2") (pintype "passive"))
      (node (ref "SW21") (pin "2") (pinfunction "2_2") (pintype "passive"))
    )
    (net (code "55") (name "Net-(D21-CATHODE)") (class "Default")
      (node (ref "D21") (pin "1") (pinfunction "CATHODE_1") (pintype "passive"))
      (node (ref "M6") (pin "2") (pinfunction "2_2") (pintype "passive"))
    )
    (net (code "56") (name "Net-(D22-ANODE)") (class "Default")
      (node (ref "D22") (pin "2") (pinfunction "ANODE_2") (pintype "passive"))
      (node (ref "SW22") (pin "2") (pinfunction "2_2") (pintype "passive"))
    )
    (net (code "57") (name "Net-(D22-CATHODE)") (class "Default")
      (node (ref "D22") (pin "1") (pinfunction "CATHODE_1") (pintype "passive"))
      (node (ref "M7") (pin "2") (pinfunction "2_2") (pintype "passive"))
    )
    (net (code "58") (name "Net-(D23-ANODE)") (class "Default")
      (node (ref "D23") (pin "2") (pinfunction "ANODE_2") (pintype "passive"))
      (node (ref "SW23") (pin "2") (pinfunction "2_2") (pintype "passive"))
    )
    (net (code "59") (name "Net-(D23-CATHODE)") (class "Default")
      (node (ref "D23") (pin "1") (pinfunction "CATHODE_1") (pintype "passive"))
      (node (ref "M11") (pin "2") (pinfunction "2_2") (pintype "passive"))
    )
    (net (code "60") (name "Net-(D24-ANODE)") (class "Default")
      (node (ref "D24") (pin "2") (pinfunction "ANODE_2") (pintype "passive"))
      (node (ref "SW24") (pin "2") (pinfunction "2_2") (pintype "passive"))
    )
    (net (code "61") (name "Net-(D24-CATHODE)") (class "Default")
      (node (ref "D24") (pin "1") (pinfunction "CATHODE_1") (pintype "passive"))
      (node (ref "M12") (pin "2") (pinfunction "2_2") (pintype "passive"))
    )
    (net (code "62") (name "Net-(D25-ANODE)") (class "Default")
      (node (ref "D25") (pin "2") (pinfunction "ANODE_2") (pintype "passive"))
      (node (ref "SW25") (pin "2") (pinfunction "2_2") (pintype "passive"))
    )
    (net (code "63") (name "Net-(D25-CATHODE)") (class "Default")
      (node (ref "D25") (pin "1") (pinfunction "CATHODE_1") (pintype "passive"))
      (node (ref "M13") (pin "2") (pinfunction "2_2") (pintype "passive"))
    )
    (net (code "64") (name "Net-(Q1-base)") (class "Default")
      (node (ref "Q1") (pin "1") (pinfunction "base_1") (pintype "passive"))
      (node (ref "R27") (pin "2") (pinfunction "2_2") (pintype "passive"))
    )
    (net (code "65") (name "Net-(R1-Pad2)") (class "Default")
      (node (ref "R1") (pin "2") (pinfunction "2_2") (pintype "passive"))
      (node (ref "SW1") (pin "3") (pinfunction "3_3") (pintype "passive"))
    )
    (net (code "66") (name "Net-(R2-Pad2)") (class "Default")
      (node (ref "R2") (pin "2") (pinfunction "2_2") (pintype "passive"))
      (node (ref "SW2") (pin "3") (pinfunction "3_3") (pintype "passive"))
    )
    (net (code "67") (name "Net-(R3-Pad2)") (class "Default")
      (node (ref "R3") (pin "2") (pinfunction "2_2") (pintype "passive"))
      (node (ref "SW3") (pin "3") (pinfunction "3_3") (pintype "passive"))
    )
    (net (code "68") (name "Net-(R4-Pad2)") (class "Default")
      (node (ref "R4") (pin "2") (pinfunction "2_2") (pintype "passive"))
      (node (ref "SW4") (pin "3") (pinfunction "3_3") (pintype "passive"))
    )
    (net (code "69") (name "Net-(R5-Pad2)") (class "Default")
      (node (ref "R5") (pin "2") (pinfunction "2_2") (pintype "passive"))
      (node (ref "SW5") (pin "3") (pinfunction "3_3") (pintype "passive"))
    )
    (net (code "70") (name "Net-(R6-Pad2)") (class "Default")
      (node (ref "R6") (pin "2") (pinfunction "2_2") (pintype "passive"))
      (node (ref "SW6") (pin "3") (pinfunction "3_3") (pintype "passive"))
    )
    (net (code "71") (name "Net-(R7-Pad2)") (class "Default")
      (node (ref "R7") (pin "2") (pinfunction "2_2") (pintype "passive"))
      (node (ref "SW7") (pin "3") (pinfunction "3_3") (pintype "passive"))
    )
    (net (code "72") (name "Net-(R8-Pad2)") (class "Default")
      (node (ref "R8") (pin "2") (pinfunction "2_2") (pintype "passive"))
      (node (ref "SW8") (pin "3") (pinfunction "3_3") (pintype "passive"))
    )
    (net (code "73") (name "Net-(R9-Pad2)") (class "Default")
      (node (ref "R9") (pin "2") (pinfunction "2_2") (pintype "passive"))
      (node (ref "SW9") (pin "3") (pinfunction "3_3") (pintype "passive"))
    )
    (net (code "74") (name "Net-(R10-Pad2)") (class "Default")
      (node (ref "R10") (pin "2") (pinfunction "2_2") (pintype "passive"))
      (node (ref "SW10") (pin "3") (pinfunction "3_3") (pintype "passive"))
    )
    (net (code "75") (name "Net-(R11-Pad2)") (class "Default")
      (node (ref "R11") (pin "2") (pinfunction "2_2") (pintype "passive"))
      (node (ref "SW11") (pin "3") (pinfunction "3_3") (pintype "passive"))
    )
    (net (code "76") (name "Net-(R12-Pad2)") (class "Default")
      (node (ref "R12") (pin "2") (pinfunction "2_2") (pintype "passive"))
      (node (ref "SW12") (pin "3") (pinfunction "3_3") (pintype "passive"))
    )
    (net (code "77") (name "Net-(R13-Pad2)") (class "Default")
      (node (ref "R13") (pin "2") (pinfunction "2_2") (pintype "passive"))
      (node (ref "SW13") (pin "3") (pinfunction "3_3") (pintype "passive"))
    )
    (net (code "78") (name "Net-(R14-Pad2)") (class "Default")
      (node (ref "R14") (pin "2") (pinfunction "2_2") (pintype "passive"))
      (node (ref "SW14") (pin "3") (pinfunction "3_3") (pintype "passive"))
    )
    (net (code "79") (name "Net-(R15-Pad2)") (class "Default")
      (node (ref "R15") (pin "2") (pinfunction "2_2") (pintype "passive"))
      (node (ref "SW15") (pin "3") (pinfunction "3_3") (pintype "passive"))
    )
    (net (code "80") (name "Net-(R16-Pad2)") (class "Default")
      (node (ref "R16") (pin "2") (pinfunction "2_2") (pintype "passive"))
      (node (ref "SW16") (pin "3") (pinfunction "3_3") (pintype "passive"))
    )
    (net (code "81") (name "Net-(R17-Pad2)") (class "Default")
      (node (ref "R17") (pin "2") (pinfunction "2_2") (pintype "passive"))
      (node (ref "SW17") (pin "3") (pinfunction "3_3") (pintype "passive"))
    )
    (net (code "82") (name "Net-(R18-Pad2)") (class "Default")
      (node (ref "R18") (pin "2") (pinfunction "2_2") (pintype "passive"))
      (node (ref "SW18") (pin "3") (pinfunction "3_3") (pintype "passive"))
    )
    (net (code "83") (name "Net-(R19-Pad2)") (class "Default")
      (node (ref "R19") (pin "2") (pinfunction "2_2") (pintype "passive"))
      (node (ref "SW19") (pin "3") (pinfunction "3_3") (pintype "passive"))
    )
    (net (code "84") (name "Net-(R20-Pad2)") (class "Default")
      (node (ref "R20") (pin "2") (pinfunction "2_2") (pintype "passive"))
      (node (ref "SW20") (pin "3") (pinfunction "3_3") (pintype "passive"))
    )
    (net (code "85") (name "Net-(R21-Pad2)") (class "Default")
      (node (ref "R21") (pin "2") (pinfunction "2_2") (pintype "passive"))
      (node (ref "SW21") (pin "3") (pinfunction "3_3") (pintype "passive"))
    )
    (net (code "86") (name "Net-(R22-Pad2)") (class "Default")
      (node (ref "R22") (pin "2") (pinfunction "2_2") (pintype "passive"))
      (node (ref "SW22") (pin "3") (pinfunction "3_3") (pintype "passive"))
    )
    (net (code "87") (name "Net-(R23-Pad2)") (class "Default")
      (node (ref "R23") (pin "2") (pinfunction "2_2") (pintype "passive"))
      (node (ref "SW23") (pin "3") (pinfunction "3_3") (pintype "passive"))
    )
    (net (code "88") (name "Net-(R24-Pad2)") (class "Default")
      (node (ref "R24") (pin "2") (pinfunction "2_2") (pintype "passive"))
      (node (ref "SW24") (pin "3") (pinfunction "3_3") (pintype "passive"))
    )
    (net (code "89") (name "Net-(R25-Pad2)") (class "Default")
      (node (ref "R25") (pin "2") (pinfunction "2_2") (pintype "passive"))
      (node (ref "SW25") (pin "3") (pinfunction "3_3") (pintype "passive"))
    )
  )
)
